# rega.net
KiCad netlist of a schematic drawn in EAGLE
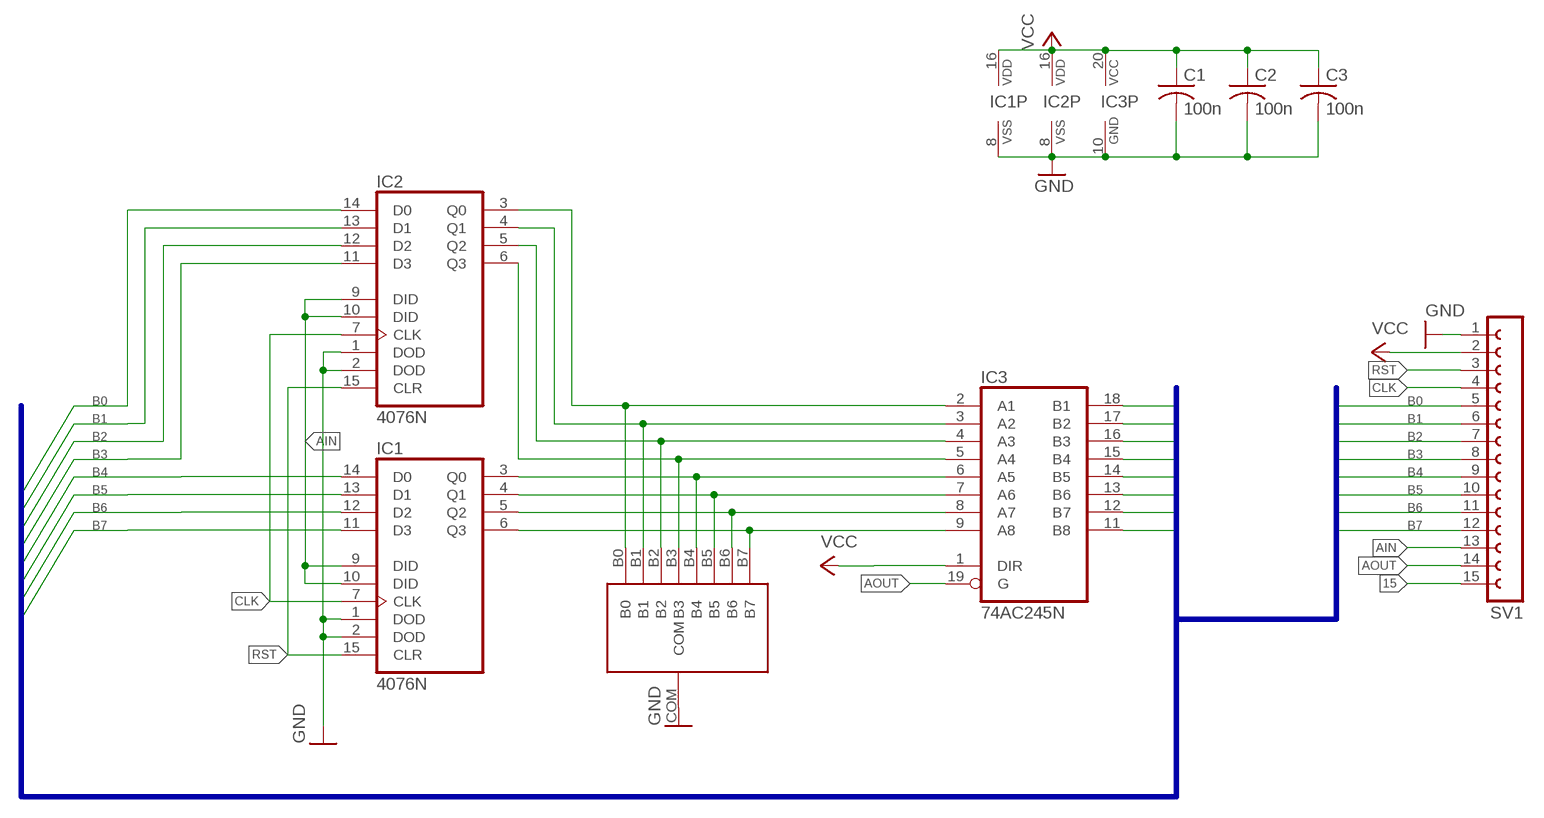
[diagram p0: schematic, sheet 1]

(export (version "E")
  (design (tool "Eeschema 10.0.6"))
  (components
    (comp (ref "C1")
      (value "100n")
      (footprint "eagle-import:C050-025X075")
      (libsource (lib "eagle-import") (part "C-US050-025X075"))
    )
    (comp (ref "C2")
      (value "100n")
      (footprint "eagle-import:C050-025X075")
      (libsource (lib "eagle-import") (part "C-US050-025X075"))
    )
    (comp (ref "C3")
      (value "100n")
      (footprint "eagle-import:C050-025X075")
      (libsource (lib "eagle-import") (part "C-US050-025X075"))
    )
    (comp (ref "IC1")
      (value "4076N")
      (footprint "eagle-import:DIL16")
      (libsource (lib "eagle-import") (part "4076N"))
    )
    (comp (ref "IC2")
      (value "4076N")
      (footprint "eagle-import:DIL16")
      (libsource (lib "eagle-import") (part "4076N"))
    )
    (comp (ref "IC3")
      (value "74AC245N")
      (footprint "eagle-import:DIL20")
      (libsource (lib "eagle-import") (part "74245NAC"))
    )
    (comp (ref "SV1")
      (value "FE15-1")
      (footprint "eagle-import:FE15")
      (libsource (lib "eagle-import") (part "FE15-1"))
    )
    (comp (ref "U$1")
      (value "LEDEDGEGRAPH")
      (footprint "eagle-import:LEDEDGEGRAPH")
      (libsource (lib "eagle-import") (part "LEDEDGEGRAPH"))
    )
  )
  (nets
    (net (code "1") (name "/B0") (class "Default")
      (node (ref "IC2") (pin "14") (pinfunction "D0_14") (pintype "input"))
      (node (ref "IC3") (pin "18") (pinfunction "B1_18") (pintype "bidirectional"))
      (node (ref "SV1") (pin "5") (pinfunction "5_5") (pintype "passive"))
    )
    (net (code "2") (name "/B1") (class "Default")
      (node (ref "IC2") (pin "13") (pinfunction "D1_13") (pintype "input"))
      (node (ref "IC3") (pin "17") (pinfunction "B2_17") (pintype "bidirectional"))
      (node (ref "SV1") (pin "6") (pinfunction "6_6") (pintype "passive"))
    )
    (net (code "3") (name "/B2") (class "Default")
      (node (ref "IC2") (pin "12") (pinfunction "D2_12") (pintype "input"))
      (node (ref "IC3") (pin "16") (pinfunction "B3_16") (pintype "bidirectional"))
      (node (ref "SV1") (pin "7") (pinfunction "7_7") (pintype "passive"))
    )
    (net (code "4") (name "/B3") (class "Default")
      (node (ref "IC2") (pin "11") (pinfunction "D3_11") (pintype "input"))
      (node (ref "IC3") (pin "15") (pinfunction "B4_15") (pintype "bidirectional"))
      (node (ref "SV1") (pin "8") (pinfunction "8_8") (pintype "passive"))
    )
    (net (code "5") (name "/B4") (class "Default")
      (node (ref "IC1") (pin "14") (pinfunction "D0_14") (pintype "input"))
      (node (ref "IC3") (pin "14") (pinfunction "B5_14") (pintype "bidirectional"))
      (node (ref "SV1") (pin "9") (pinfunction "9_9") (pintype "passive"))
    )
    (net (code "6") (name "/B5") (class "Default")
      (node (ref "IC1") (pin "13") (pinfunction "D1_13") (pintype "input"))
      (node (ref "IC3") (pin "13") (pinfunction "B6_13") (pintype "bidirectional"))
      (node (ref "SV1") (pin "10") (pinfunction "10_10") (pintype "passive"))
    )
    (net (code "7") (name "/B6") (class "Default")
      (node (ref "IC1") (pin "12") (pinfunction "D2_12") (pintype "input"))
      (node (ref "IC3") (pin "12") (pinfunction "B7_12") (pintype "bidirectional"))
      (node (ref "SV1") (pin "11") (pinfunction "11_11") (pintype "passive"))
    )
    (net (code "8") (name "/B7") (class "Default")
      (node (ref "IC1") (pin "11") (pinfunction "D3_11") (pintype "input"))
      (node (ref "IC3") (pin "11") (pinfunction "B8_11") (pintype "bidirectional"))
      (node (ref "SV1") (pin "12") (pinfunction "12_12") (pintype "passive"))
    )
    (net (code "9") (name "15") (class "Default")
      (node (ref "SV1") (pin "15") (pinfunction "15_15") (pintype "passive"))
    )
    (net (code "10") (name "AIN") (class "Default")
      (node (ref "IC1") (pin "10") (pinfunction "DID_10") (pintype "input"))
      (node (ref "IC1") (pin "9") (pinfunction "DID_9") (pintype "input"))
      (node (ref "IC2") (pin "10") (pinfunction "DID_10") (pintype "input"))
      (node (ref "IC2") (pin "9") (pinfunction "DID_9") (pintype "input"))
      (node (ref "SV1") (pin "13") (pinfunction "13_13") (pintype "passive"))
    )
    (net (code "11") (name "AOUT") (class "Default")
      (node (ref "IC3") (pin "19") (pinfunction "G_19") (pintype "input"))
      (node (ref "SV1") (pin "14") (pinfunction "14_14") (pintype "passive"))
    )
    (net (code "12") (name "CLK") (class "Default")
      (node (ref "IC1") (pin "7") (pinfunction "CLK_7") (pintype "input"))
      (node (ref "IC2") (pin "7") (pinfunction "CLK_7") (pintype "input"))
      (node (ref "SV1") (pin "4") (pinfunction "4_4") (pintype "passive"))
    )
    (net (code "13") (name "GND") (class "Default")
      (node (ref "C1") (pin "2") (pinfunction "2_2") (pintype "passive"))
      (node (ref "C2") (pin "2") (pinfunction "2_2") (pintype "passive"))
      (node (ref "C3") (pin "2") (pinfunction "2_2") (pintype "passive"))
      (node (ref "IC1") (pin "1") (pinfunction "DOD_1") (pintype "input"))
      (node (ref "IC1") (pin "2") (pinfunction "DOD_2") (pintype "input"))
      (node (ref "IC1") (pin "8") (pinfunction "VSS_8") (pintype "power_in"))
      (node (ref "IC2") (pin "1") (pinfunction "DOD_1") (pintype "input"))
      (node (ref "IC2") (pin "2") (pinfunction "DOD_2") (pintype "input"))
      (node (ref "IC2") (pin "8") (pinfunction "VSS_8") (pintype "power_in"))
      (node (ref "IC3") (pin "10") (pinfunction "GND_10") (pintype "power_in"))
      (node (ref "SV1") (pin "1") (pinfunction "1_1") (pintype "passive"))
      (node (ref "U$1") (pin "COM") (pinfunction "COM_COM") (pintype "bidirectional"))
    )
    (net (code "14") (name "Net-(IC1A-Q0)") (class "Default")
      (node (ref "IC1") (pin "3") (pinfunction "Q0_3") (pintype "output"))
      (node (ref "IC3") (pin "6") (pinfunction "A5_6") (pintype "bidirectional"))
      (node (ref "U$1") (pin "B4") (pinfunction "B4_B4") (pintype "bidirectional"))
    )
    (net (code "15") (name "Net-(IC1A-Q1)") (class "Default")
      (node (ref "IC1") (pin "4") (pinfunction "Q1_4") (pintype "output"))
      (node (ref "IC3") (pin "7") (pinfunction "A6_7") (pintype "bidirectional"))
      (node (ref "U$1") (pin "B5") (pinfunction "B5_B5") (pintype "bidirectional"))
    )
    (net (code "16") (name "Net-(IC1A-Q2)") (class "Default")
      (node (ref "IC1") (pin "5") (pinfunction "Q2_5") (pintype "output"))
      (node (ref "IC3") (pin "8") (pinfunction "A7_8") (pintype "bidirectional"))
      (node (ref "U$1") (pin "B6") (pinfunction "B6_B6") (pintype "bidirectional"))
    )
    (net (code "17") (name "Net-(IC1A-Q3)") (class "Default")
      (node (ref "IC1") (pin "6") (pinfunction "Q3_6") (pintype "output"))
      (node (ref "IC3") (pin "9") (pinfunction "A8_9") (pintype "bidirectional"))
      (node (ref "U$1") (pin "B7") (pinfunction "B7_B7") (pintype "bidirectional"))
    )
    (net (code "18") (name "Net-(IC2A-Q0)") (class "Default")
      (node (ref "IC2") (pin "3") (pinfunction "Q0_3") (pintype "output"))
      (node (ref "IC3") (pin "2") (pinfunction "A1_2") (pintype "bidirectional"))
      (node (ref "U$1") (pin "B0") (pinfunction "B0_B0") (pintype "bidirectional"))
    )
    (net (code "19") (name "Net-(IC2A-Q1)") (class "Default")
      (node (ref "IC2") (pin "4") (pinfunction "Q1_4") (pintype "output"))
      (node (ref "IC3") (pin "3") (pinfunction "A2_3") (pintype "bidirectional"))
      (node (ref "U$1") (pin "B1") (pinfunction "B1_B1") (pintype "bidirectional"))
    )
    (net (code "20") (name "Net-(IC2A-Q2)") (class "Default")
      (node (ref "IC2") (pin "5") (pinfunction "Q2_5") (pintype "output"))
      (node (ref "IC3") (pin "4") (pinfunction "A3_4") (pintype "bidirectional"))
      (node (ref "U$1") (pin "B2") (pinfunction "B2_B2") (pintype "bidirectional"))
    )
    (net (code "21") (name "Net-(IC2A-Q3)") (class "Default")
      (node (ref "IC2") (pin "6") (pinfunction "Q3_6") (pintype "output"))
      (node (ref "IC3") (pin "5") (pinfunction "A4_5") (pintype "bidirectional"))
      (node (ref "U$1") (pin "B3") (pinfunction "B3_B3") (pintype "bidirectional"))
    )
    (net (code "22") (name "RST") (class "Default")
      (node (ref "IC1") (pin "15") (pinfunction "CLR_15") (pintype "input"))
      (node (ref "IC2") (pin "15") (pinfunction "CLR_15") (pintype "input"))
      (node (ref "SV1") (pin "3") (pinfunction "3_3") (pintype "passive"))
    )
    (net (code "23") (name "VCC") (class "Default")
      (node (ref "C1") (pin "1") (pinfunction "1_1") (pintype "passive"))
      (node (ref "C2") (pin "1") (pinfunction "1_1") (pintype "passive"))
      (node (ref "C3") (pin "1") (pinfunction "1_1") (pintype "passive"))
      (node (ref "IC1") (pin "16") (pinfunction "VDD_16") (pintype "power_in"))
      (node (ref "IC2") (pin "16") (pinfunction "VDD_16") (pintype "power_in"))
      (node (ref "IC3") (pin "1") (pinfunction "DIR_1") (pintype "input"))
      (node (ref "IC3") (pin "20") (pinfunction "VCC_20") (pintype "power_in"))
      (node (ref "SV1") (pin "2") (pinfunction "2_2") (pintype "passive"))
    )
  )
)
